# BW1098OAK_RIGHT_OV9282.net
KiCad netlist of a schematic drawn in Altium Designer
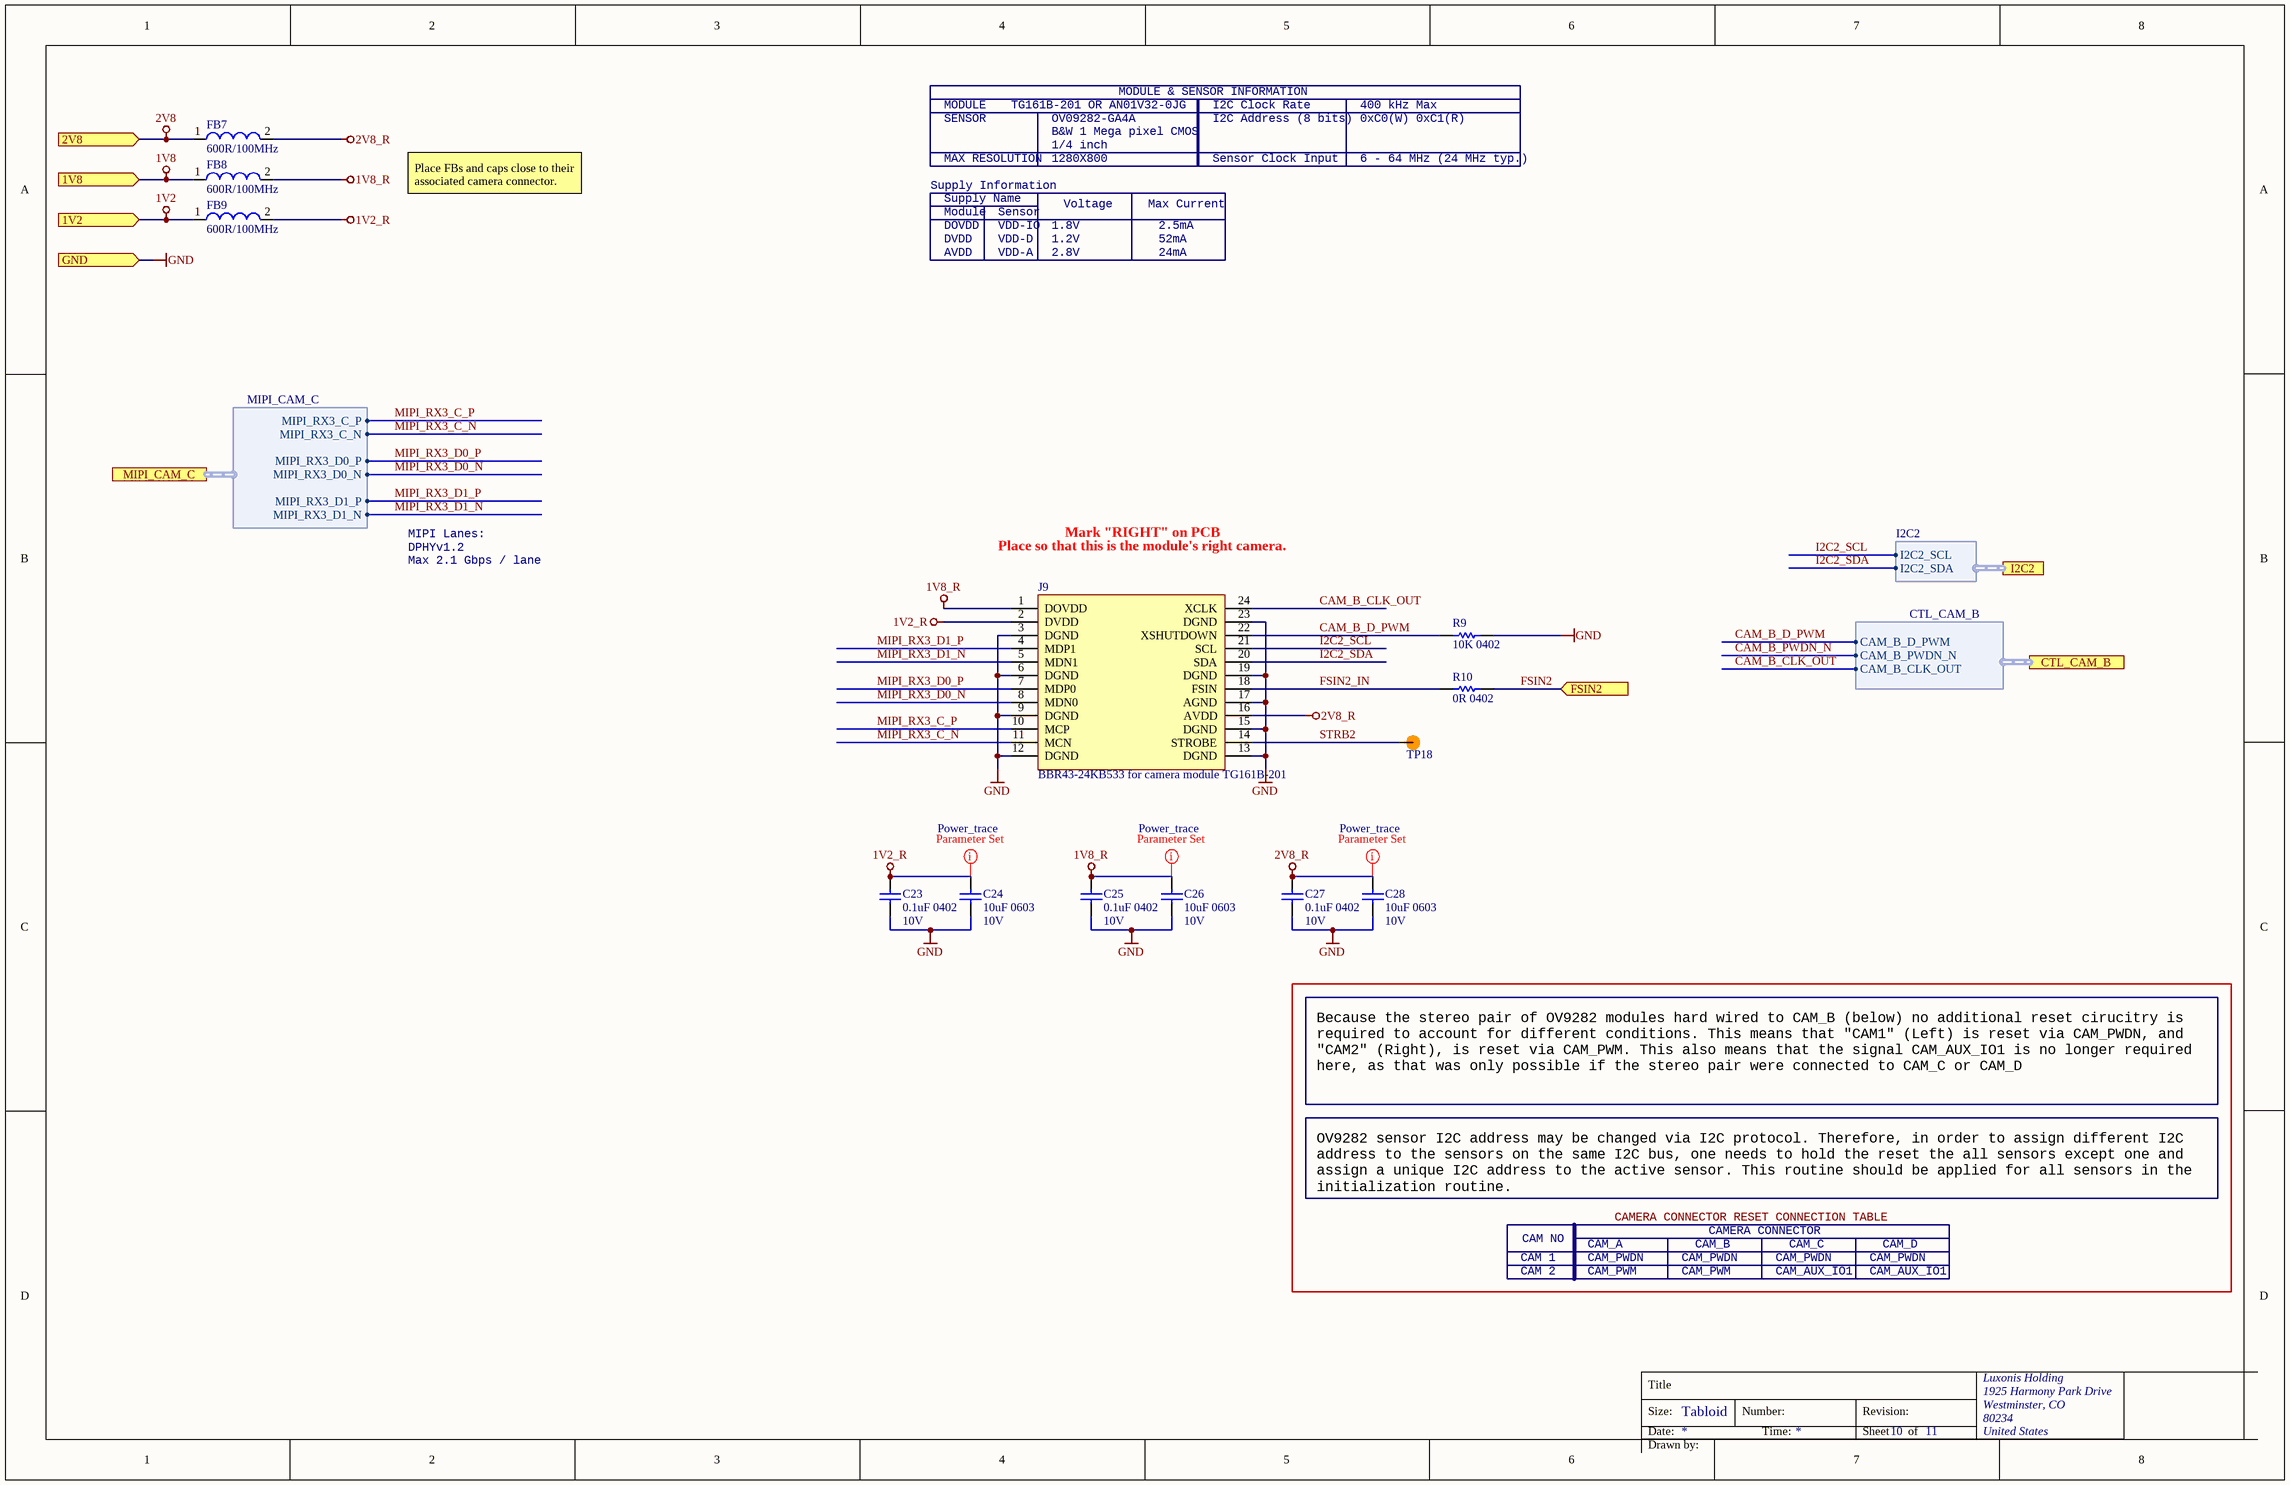
[diagram p0: BW1098OAK_RIGHT_OV9282.SchDoc]

(export (version "E")
  (design (tool "Eeschema 10.0.6"))
  (components
    (comp (ref "C23")
      (value "0.1uF 0402")
      (footprint "CAP_Altium_Vault_Generic:CAPC0402(1005)70_L")
      (description "CAP CER 0.1UF 10V X7R 0402 5%")
      (fields (field (name "TOLERANCE") "5%") (field (name "VOLTAGE RATING") "10V"))
      (libsource (lib "LuxonisMaster") (part "GRM155R71A104JA01D"))
    )
    (comp (ref "C24")
      (value "10uF 0603")
      (footprint "CAP_Altium_Vault_Generic:CAPC0603(1608)100_L")
      (description "CAP CER 10UF 10V X5R 0603 20%")
      (fields (field (name "TOLERANCE") "20%") (field (name "VOLTAGE RATING") "10V"))
      (libsource (lib "LuxonisMaster") (part "GRM188R61A106ME69D"))
    )
    (comp (ref "C25")
      (value "0.1uF 0402")
      (footprint "CAP_Altium_Vault_Generic:CAPC0402(1005)70_L")
      (description "CAP CER 0.1UF 10V X7R 0402 5%")
      (fields (field (name "TOLERANCE") "5%") (field (name "VOLTAGE RATING") "10V"))
      (libsource (lib "LuxonisMaster") (part "GRM155R71A104JA01D"))
    )
    (comp (ref "C26")
      (value "10uF 0603")
      (footprint "CAP_Altium_Vault_Generic:CAPC0603(1608)100_L")
      (description "CAP CER 10UF 10V X5R 0603 20%")
      (fields (field (name "TOLERANCE") "20%") (field (name "VOLTAGE RATING") "10V"))
      (libsource (lib "LuxonisMaster") (part "GRM188R61A106ME69D"))
    )
    (comp (ref "C27")
      (value "0.1uF 0402")
      (footprint "CAP_Altium_Vault_Generic:CAPC0402(1005)70_L")
      (description "CAP CER 0.1UF 10V X7R 0402 5%")
      (fields (field (name "TOLERANCE") "5%") (field (name "VOLTAGE RATING") "10V"))
      (libsource (lib "LuxonisMaster") (part "GRM155R71A104JA01D"))
    )
    (comp (ref "C28")
      (value "10uF 0603")
      (footprint "CAP_Altium_Vault_Generic:CAPC0603(1608)100_L")
      (description "CAP CER 10UF 10V X5R 0603 20%")
      (fields (field (name "TOLERANCE") "20%") (field (name "VOLTAGE RATING") "10V"))
      (libsource (lib "LuxonisMaster") (part "GRM188R61A106ME69D"))
    )
    (comp (ref "FB7")
      (value "600R/100MHz")
      (footprint "LuxonisMaster:2508056017Y2")
      (description "FERRITE BEAD, 0.1OHM, 2A, 0805, 600R/100MHz")
      (fields (field (name "TOLERANCE") "25%"))
      (libsource (lib "LuxonisMaster") (part "2508056017Y2"))
    )
    (comp (ref "FB8")
      (value "600R/100MHz")
      (footprint "LuxonisMaster:2508056017Y2")
      (description "FERRITE BEAD, 0.1OHM, 2A, 0805, 600R/100MHz")
      (fields (field (name "TOLERANCE") "25%"))
      (libsource (lib "LuxonisMaster") (part "2508056017Y2"))
    )
    (comp (ref "FB9")
      (value "600R/100MHz")
      (footprint "LuxonisMaster:2508056017Y2")
      (description "FERRITE BEAD, 0.1OHM, 2A, 0805, 600R/100MHz")
      (fields (field (name "TOLERANCE") "25%"))
      (libsource (lib "LuxonisMaster") (part "2508056017Y2"))
    )
    (comp (ref "J9")
      (value "BBR43-24KB533 for camera module TG161B-201")
      (footprint "LuxonisMaster:TG161B-201 / AN01V32 - Board Wrap (7mm setback) MinPads")
      (description "CONN 24 way, 2 row board to board connector SMD")
      (libsource (lib "LuxonisMaster") (part "TG161B-201_Connector"))
    )
    (comp (ref "R9")
      (value "10K 0402")
      (footprint "RES_Altium_Vault_Generic:RESC0402(1005)_L")
      (fields (field (name "TOLERANCE") "1%"))
      (libsource (lib "LuxonisMaster") (part "RC0402FR-1310KL"))
    )
    (comp (ref "R10")
      (value "0R 0402")
      (footprint "RES_Altium_Vault_Generic:RESC0402(1005)_L")
      (description "RES SMD 0 OHM JUMPER 1/16W 0402")
      (fields (field (name "TOLERANCE") "5%"))
      (libsource (lib "LuxonisMaster") (part "CRCW04020000Z0ED"))
    )
    (comp (ref "TP18")
      (value "TP100_200_NS")
      (footprint "LuxonisMaster:TP100_200_NS")
      (libsource (lib "LuxonisMaster") (part "TEST_POINT"))
    )
  )
  (nets
    (net (code "4") (name "/CAM_B_CLK_OUT") (class "Default")
      (node (ref "J9") (pin "24") (pinfunction "XCLK_24") (pintype "passive"))
    )
    (net (code "5") (name "/CAM_B_D_PWM") (class "Default")
      (node (ref "J9") (pin "22") (pinfunction "XSHUTDOWN_22") (pintype "passive"))
      (node (ref "R9") (pin "1") (pinfunction "1_1") (pintype "passive"))
    )
    (net (code "7") (name "/FSIN2") (class "Default")
      (node (ref "R10") (pin "2") (pinfunction "2_2") (pintype "passive"))
    )
    (net (code "8") (name "/FSIN2_IN") (class "Default")
      (node (ref "J9") (pin "18") (pinfunction "FSIN_18") (pintype "passive"))
      (node (ref "R10") (pin "1") (pinfunction "1_1") (pintype "passive"))
    )
    (net (code "9") (name "/I2C2_SCL") (class "Default")
      (node (ref "J9") (pin "21") (pinfunction "SCL_21") (pintype "passive"))
    )
    (net (code "10") (name "/I2C2_SDA") (class "Default")
      (node (ref "J9") (pin "20") (pinfunction "SDA_20") (pintype "passive"))
    )
    (net (code "11") (name "/MIPI_RX3_C_N") (class "Default")
      (node (ref "J9") (pin "11") (pinfunction "MCN_11") (pintype "passive"))
    )
    (net (code "12") (name "/MIPI_RX3_C_P") (class "Default")
      (node (ref "J9") (pin "10") (pinfunction "MCP_10") (pintype "passive"))
    )
    (net (code "13") (name "/MIPI_RX3_D0_N") (class "Default")
      (node (ref "J9") (pin "8") (pinfunction "MDN0_8") (pintype "passive"))
    )
    (net (code "14") (name "/MIPI_RX3_D0_P") (class "Default")
      (node (ref "J9") (pin "7") (pinfunction "MDP0_7") (pintype "passive"))
    )
    (net (code "15") (name "/MIPI_RX3_D1_N") (class "Default")
      (node (ref "J9") (pin "5") (pinfunction "MDN1_5") (pintype "passive"))
    )
    (net (code "16") (name "/MIPI_RX3_D1_P") (class "Default")
      (node (ref "J9") (pin "4") (pinfunction "MDP1_4") (pintype "passive"))
    )
    (net (code "17") (name "/STRB2") (class "Default")
      (node (ref "J9") (pin "14") (pinfunction "STROBE_14") (pintype "passive"))
      (node (ref "TP18") (pin "1") (pintype "passive"))
    )
    (net (code "21") (name "1V2") (class "Default")
      (node (ref "FB9") (pin "1") (pinfunction "1_1") (pintype "passive"))
    )
    (net (code "22") (name "1V2_R") (class "Default")
      (node (ref "C23") (pin "2") (pinfunction "2_2") (pintype "passive"))
      (node (ref "C24") (pin "2") (pinfunction "2_2") (pintype "passive"))
      (node (ref "FB9") (pin "2") (pinfunction "2_2") (pintype "passive"))
      (node (ref "J9") (pin "2") (pinfunction "DVDD_2") (pintype "passive"))
    )
    (net (code "23") (name "1V8") (class "Default")
      (node (ref "FB8") (pin "1") (pinfunction "1_1") (pintype "passive"))
    )
    (net (code "24") (name "1V8_R") (class "Default")
      (node (ref "C25") (pin "2") (pinfunction "2_2") (pintype "passive"))
      (node (ref "C26") (pin "2") (pinfunction "2_2") (pintype "passive"))
      (node (ref "FB8") (pin "2") (pinfunction "2_2") (pintype "passive"))
      (node (ref "J9") (pin "1") (pinfunction "DOVDD_1") (pintype "passive"))
    )
    (net (code "25") (name "2V8") (class "Default")
      (node (ref "FB7") (pin "1") (pinfunction "1_1") (pintype "passive"))
    )
    (net (code "26") (name "2V8_R") (class "Default")
      (node (ref "C27") (pin "2") (pinfunction "2_2") (pintype "passive"))
      (node (ref "C28") (pin "2") (pinfunction "2_2") (pintype "passive"))
      (node (ref "FB7") (pin "2") (pinfunction "2_2") (pintype "passive"))
      (node (ref "J9") (pin "16") (pinfunction "AVDD_16") (pintype "passive"))
    )
    (net (code "27") (name "GND") (class "Default")
      (node (ref "C23") (pin "1") (pinfunction "1_1") (pintype "passive"))
      (node (ref "C24") (pin "1") (pinfunction "1_1") (pintype "passive"))
      (node (ref "C25") (pin "1") (pinfunction "1_1") (pintype "passive"))
      (node (ref "C26") (pin "1") (pinfunction "1_1") (pintype "passive"))
      (node (ref "C27") (pin "1") (pinfunction "1_1") (pintype "passive"))
      (node (ref "C28") (pin "1") (pinfunction "1_1") (pintype "passive"))
      (node (ref "J9") (pin "12") (pinfunction "DGND_12") (pintype "passive"))
      (node (ref "J9") (pin "13") (pinfunction "DGND_13") (pintype "passive"))
      (node (ref "J9") (pin "15") (pinfunction "DGND_15") (pintype "passive"))
      (node (ref "J9") (pin "17") (pinfunction "AGND_17") (pintype "passive"))
      (node (ref "J9") (pin "19") (pinfunction "DGND_19") (pintype "passive"))
      (node (ref "J9") (pin "23") (pinfunction "DGND_23") (pintype "passive"))
      (node (ref "J9") (pin "3") (pinfunction "DGND_3") (pintype "passive"))
      (node (ref "J9") (pin "6") (pinfunction "DGND_6") (pintype "passive"))
      (node (ref "J9") (pin "9") (pinfunction "DGND_9") (pintype "passive"))
      (node (ref "R9") (pin "2") (pinfunction "2_2") (pintype "passive"))
    )
  )
)
